# lcd-i2c.net
KiCad netlist of a schematic drawn in EAGLE
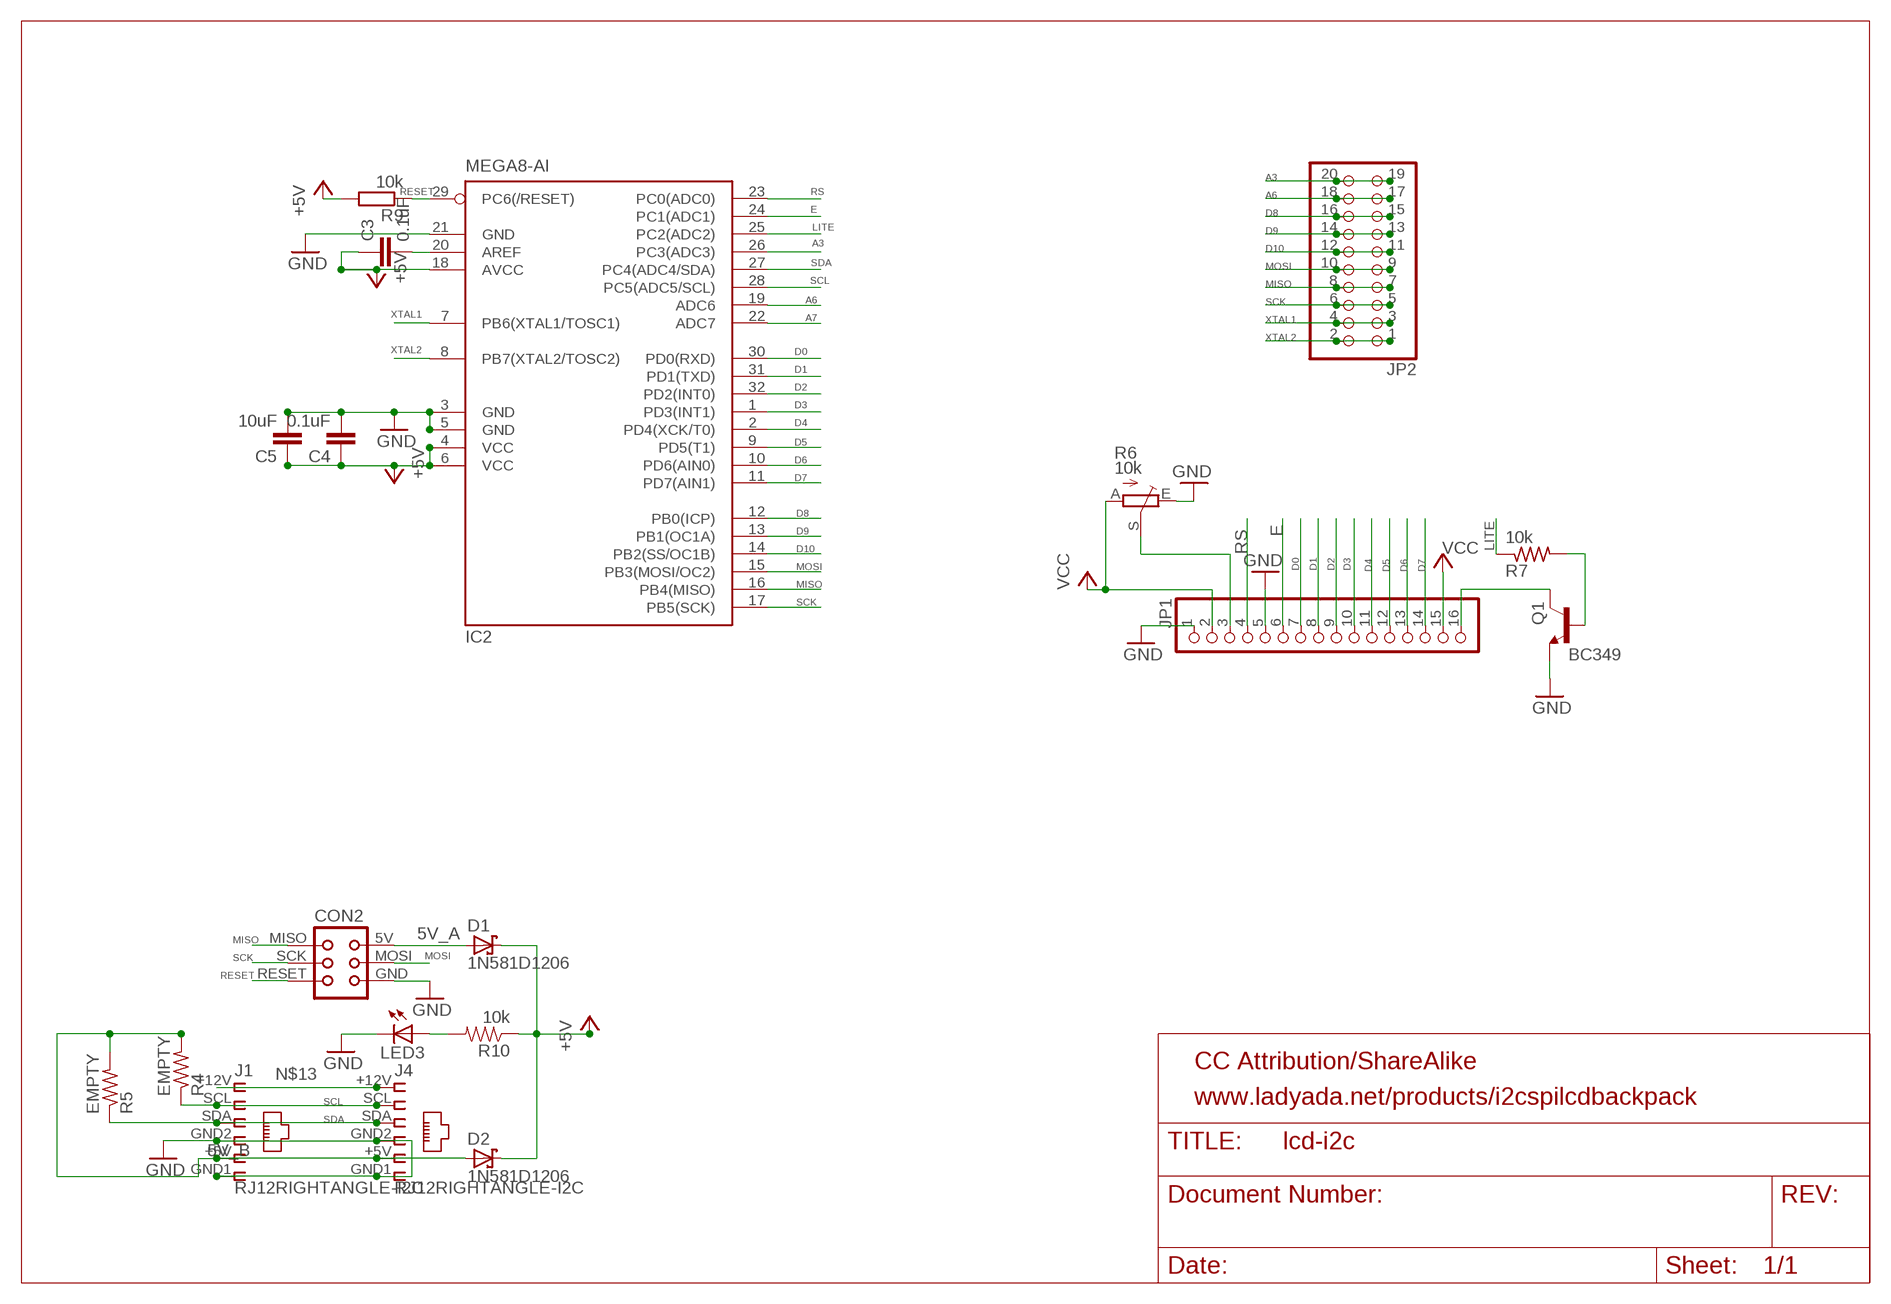
[diagram p0: schematic, sheet 1]

(export (version "E")
  (design (tool "Eeschema 10.0.6"))
  (components
    (comp (ref "C3")
      (value "0.1uF")
      (footprint "eagle-import:C1206")
      (libsource (lib "eagle-import") (part "C-EUC1206"))
    )
    (comp (ref "C4")
      (value "0.1uF")
      (footprint "eagle-import:C1206")
      (libsource (lib "eagle-import") (part "C-EUC1206"))
    )
    (comp (ref "C5")
      (value "10uF")
      (footprint "eagle-import:C1206")
      (libsource (lib "eagle-import") (part "C-EUC1206"))
    )
    (comp (ref "CON2")
      (value "TINYISPTAG")
      (footprint "eagle-import:TC2030-MCP")
      (libsource (lib "eagle-import") (part "TINYISPTAG"))
    )
    (comp (ref "D1")
      (value "1N581D1206")
      (footprint "eagle-import:LED-1206")
      (libsource (lib "eagle-import") (part "1N581D1206"))
    )
    (comp (ref "D2")
      (value "1N581D1206")
      (footprint "eagle-import:LED-1206")
      (libsource (lib "eagle-import") (part "1N581D1206"))
    )
    (comp (ref "IC2")
      (value "MEGA8-AI")
      (footprint "eagle-import:TQFP32-08")
      (fields (field (name "MPN") "ATMEGA8-16AU"))
      (libsource (lib "eagle-import") (part "MEGA8-AI"))
    )
    (comp (ref "J1")
      (value "RJ12RIGHTANGLE-I2C")
      (footprint "eagle-import:RJ12-RIGHTANGLE-I2C")
      (libsource (lib "eagle-import") (part "RJ12RIGHTANGLE-I2C"))
    )
    (comp (ref "J4")
      (value "RJ12RIGHTANGLE-I2C")
      (footprint "eagle-import:RJ12-RIGHTANGLE-I2C")
      (libsource (lib "eagle-import") (part "RJ12RIGHTANGLE-I2C"))
    )
    (comp (ref "JP1")
      (value "PINHD-1X16")
      (footprint "eagle-import:1X16")
      (libsource (lib "eagle-import") (part "PINHD-1X16"))
    )
    (comp (ref "JP2")
      (value "PINHD-2X10")
      (footprint "eagle-import:2X10")
      (libsource (lib "eagle-import") (part "PINHD-2X10"))
    )
    (comp (ref "LED3")
      (value "LEDCHIP-LED0603")
      (footprint "eagle-import:CHIP-LED0603")
      (libsource (lib "eagle-import") (part "LEDCHIP-LED0603"))
    )
    (comp (ref "Q1")
      (value "BC349")
      (footprint "eagle-import:TO92-EBC")
      (libsource (lib "eagle-import") (part "-NPN-TO92-EBCBC317"))
    )
    (comp (ref "R4")
      (value "EMPTY")
      (footprint "eagle-import:M1206")
      (libsource (lib "eagle-import") (part "R-US_M1206"))
    )
    (comp (ref "R5")
      (value "EMPTY")
      (footprint "eagle-import:M1206")
      (libsource (lib "eagle-import") (part "R-US_M1206"))
    )
    (comp (ref "R6")
      (value "10k")
      (footprint "eagle-import:CA6V")
      (libsource (lib "eagle-import") (part "TRIM_EU-CA6V"))
    )
    (comp (ref "R7")
      (value "10k")
      (footprint "eagle-import:M1206")
      (libsource (lib "eagle-import") (part "R-US_M1206"))
    )
    (comp (ref "R9")
      (value "10k")
      (footprint "eagle-import:M1206")
      (libsource (lib "eagle-import") (part "R-EU_M1206"))
    )
    (comp (ref "R10")
      (value "10k")
      (footprint "eagle-import:0603-RES")
      (libsource (lib "eagle-import") (part "RESISTOR0603-RES"))
    )
  )
  (nets
    (net (code "1") (name "+5V") (class "Default")
      (node (ref "C3") (pin "1") (pinfunction "1_1") (pintype "passive"))
      (node (ref "C4") (pin "1") (pinfunction "1_1") (pintype "passive"))
      (node (ref "C5") (pin "1") (pinfunction "1_1") (pintype "passive"))
      (node (ref "D1") (pin "C") (pinfunction "C_C") (pintype "passive"))
      (node (ref "D2") (pin "C") (pinfunction "C_C") (pintype "passive"))
      (node (ref "IC2") (pin "18") (pinfunction "AVCC_18") (pintype "power_in"))
      (node (ref "IC2") (pin "4") (pinfunction "VCC_4") (pintype "power_in"))
      (node (ref "IC2") (pin "6") (pinfunction "VCC_6") (pintype "power_in"))
      (node (ref "R10") (pin "1") (pinfunction "1_1") (pintype "passive"))
      (node (ref "R9") (pin "2") (pinfunction "2_2") (pintype "passive"))
    )
    (net (code "2") (name "/5V_A") (class "Default")
      (node (ref "CON2") (pin "5V") (pinfunction "VCC_5V") (pintype "passive"))
      (node (ref "D1") (pin "A") (pinfunction "A_A") (pintype "passive"))
    )
    (net (code "3") (name "/5V_B") (class "Default")
      (node (ref "D2") (pin "A") (pinfunction "A_A") (pintype "passive"))
      (node (ref "J1") (pin "+5V") (pinfunction "5_+5V") (pintype "bidirectional"))
      (node (ref "J4") (pin "+5V") (pinfunction "5_+5V") (pintype "bidirectional"))
      (node (ref "R4") (pin "2") (pinfunction "2_2") (pintype "passive"))
      (node (ref "R5") (pin "2") (pinfunction "2_2") (pintype "passive"))
    )
    (net (code "4") (name "/A3") (class "Default")
      (node (ref "IC2") (pin "26") (pinfunction "PC3(ADC3)_26") (pintype "bidirectional"))
      (node (ref "JP2") (pin "19") (pinfunction "19_19") (pintype "passive"))
      (node (ref "JP2") (pin "20") (pinfunction "20_20") (pintype "passive"))
    )
    (net (code "5") (name "/A6") (class "Default")
      (node (ref "IC2") (pin "19") (pinfunction "ADC6_19") (pintype "bidirectional"))
      (node (ref "JP2") (pin "17") (pinfunction "17_17") (pintype "passive"))
      (node (ref "JP2") (pin "18") (pinfunction "18_18") (pintype "passive"))
    )
    (net (code "6") (name "/A7") (class "Default")
      (node (ref "IC2") (pin "22") (pinfunction "ADC7_22") (pintype "bidirectional"))
    )
    (net (code "7") (name "/D0") (class "Default")
      (node (ref "IC2") (pin "30") (pinfunction "PD0(RXD)_30") (pintype "bidirectional"))
      (node (ref "JP1") (pin "7") (pinfunction "7_7") (pintype "passive"))
    )
    (net (code "8") (name "/D1") (class "Default")
      (node (ref "IC2") (pin "31") (pinfunction "PD1(TXD)_31") (pintype "bidirectional"))
      (node (ref "JP1") (pin "8") (pinfunction "8_8") (pintype "passive"))
    )
    (net (code "9") (name "/D2") (class "Default")
      (node (ref "IC2") (pin "32") (pinfunction "PD2(INT0)_32") (pintype "bidirectional"))
      (node (ref "JP1") (pin "9") (pinfunction "9_9") (pintype "passive"))
    )
    (net (code "10") (name "/D3") (class "Default")
      (node (ref "IC2") (pin "1") (pinfunction "PD3(INT1)_1") (pintype "bidirectional"))
      (node (ref "JP1") (pin "10") (pinfunction "10_10") (pintype "passive"))
    )
    (net (code "11") (name "/D4") (class "Default")
      (node (ref "IC2") (pin "2") (pinfunction "PD4(XCK/T0)_2") (pintype "bidirectional"))
      (node (ref "JP1") (pin "11") (pinfunction "11_11") (pintype "passive"))
    )
    (net (code "12") (name "/D5") (class "Default")
      (node (ref "IC2") (pin "9") (pinfunction "PD5(T1)_9") (pintype "bidirectional"))
      (node (ref "JP1") (pin "12") (pinfunction "12_12") (pintype "passive"))
    )
    (net (code "13") (name "/D6") (class "Default")
      (node (ref "IC2") (pin "10") (pinfunction "PD6(AIN0)_10") (pintype "bidirectional"))
      (node (ref "JP1") (pin "13") (pinfunction "13_13") (pintype "passive"))
    )
    (net (code "14") (name "/D7") (class "Default")
      (node (ref "IC2") (pin "11") (pinfunction "PD7(AIN1)_11") (pintype "bidirectional"))
      (node (ref "JP1") (pin "14") (pinfunction "14_14") (pintype "passive"))
    )
    (net (code "15") (name "/D8") (class "Default")
      (node (ref "IC2") (pin "12") (pinfunction "PB0(ICP)_12") (pintype "bidirectional"))
      (node (ref "JP2") (pin "15") (pinfunction "15_15") (pintype "passive"))
      (node (ref "JP2") (pin "16") (pinfunction "16_16") (pintype "passive"))
    )
    (net (code "16") (name "/D9") (class "Default")
      (node (ref "IC2") (pin "13") (pinfunction "PB1(OC1A)_13") (pintype "bidirectional"))
      (node (ref "JP2") (pin "13") (pinfunction "13_13") (pintype "passive"))
      (node (ref "JP2") (pin "14") (pinfunction "14_14") (pintype "passive"))
    )
    (net (code "17") (name "/D10") (class "Default")
      (node (ref "IC2") (pin "14") (pinfunction "PB2(SS/OC1B)_14") (pintype "bidirectional"))
      (node (ref "JP2") (pin "11") (pinfunction "11_11") (pintype "passive"))
      (node (ref "JP2") (pin "12") (pinfunction "12_12") (pintype "passive"))
    )
    (net (code "18") (name "/E") (class "Default")
      (node (ref "IC2") (pin "24") (pinfunction "PC1(ADC1)_24") (pintype "bidirectional"))
      (node (ref "JP1") (pin "6") (pinfunction "6_6") (pintype "passive"))
    )
    (net (code "19") (name "/LITE") (class "Default")
      (node (ref "IC2") (pin "25") (pinfunction "PC2(ADC2)_25") (pintype "bidirectional"))
      (node (ref "R7") (pin "1") (pinfunction "1_1") (pintype "passive"))
    )
    (net (code "20") (name "/MISO") (class "Default")
      (node (ref "CON2") (pin "MISO") (pinfunction "MISO_MISO") (pintype "passive"))
      (node (ref "IC2") (pin "16") (pinfunction "PB4(MISO)_16") (pintype "bidirectional"))
      (node (ref "JP2") (pin "7") (pinfunction "7_7") (pintype "passive"))
      (node (ref "JP2") (pin "8") (pinfunction "8_8") (pintype "passive"))
    )
    (net (code "21") (name "/MOSI") (class "Default")
      (node (ref "CON2") (pin "MOSI") (pinfunction "MOSI_MOSI") (pintype "passive"))
      (node (ref "IC2") (pin "15") (pinfunction "PB3(MOSI/OC2)_15") (pintype "bidirectional"))
      (node (ref "JP2") (pin "10") (pinfunction "10_10") (pintype "passive"))
      (node (ref "JP2") (pin "9") (pinfunction "9_9") (pintype "passive"))
    )
    (net (code "22") (name "/N$13") (class "Default")
      (node (ref "J1") (pin "+12V") (pinfunction "1_+12V") (pintype "bidirectional"))
      (node (ref "J4") (pin "+12V") (pinfunction "1_+12V") (pintype "bidirectional"))
    )
    (net (code "23") (name "/RESET") (class "Default")
      (node (ref "CON2") (pin "RESET") (pinfunction "RESET_RESET") (pintype "passive"))
      (node (ref "IC2") (pin "29") (pinfunction "PC6(/RESET)_29") (pintype "bidirectional"))
      (node (ref "R9") (pin "1") (pinfunction "1_1") (pintype "passive"))
    )
    (net (code "24") (name "/RS") (class "Default")
      (node (ref "IC2") (pin "23") (pinfunction "PC0(ADC0)_23") (pintype "bidirectional"))
      (node (ref "JP1") (pin "4") (pinfunction "4_4") (pintype "passive"))
    )
    (net (code "25") (name "/SCK") (class "Default")
      (node (ref "CON2") (pin "SCK") (pinfunction "SCK_SCK") (pintype "passive"))
      (node (ref "IC2") (pin "17") (pinfunction "PB5(SCK)_17") (pintype "bidirectional"))
      (node (ref "JP2") (pin "5") (pinfunction "5_5") (pintype "passive"))
      (node (ref "JP2") (pin "6") (pinfunction "6_6") (pintype "passive"))
    )
    (net (code "26") (name "/SCL") (class "Default")
      (node (ref "IC2") (pin "28") (pinfunction "PC5(ADC5/SCL)_28") (pintype "bidirectional"))
      (node (ref "J1") (pin "SCL") (pinfunction "2_SCL") (pintype "bidirectional"))
      (node (ref "J4") (pin "SCL") (pinfunction "2_SCL") (pintype "bidirectional"))
      (node (ref "R4") (pin "1") (pinfunction "1_1") (pintype "passive"))
    )
    (net (code "27") (name "/SDA") (class "Default")
      (node (ref "IC2") (pin "27") (pinfunction "PC4(ADC4/SDA)_27") (pintype "bidirectional"))
      (node (ref "J1") (pin "SDA") (pinfunction "3_SDA") (pintype "bidirectional"))
      (node (ref "J4") (pin "SDA") (pinfunction "3_SDA") (pintype "bidirectional"))
      (node (ref "R5") (pin "1") (pinfunction "1_1") (pintype "passive"))
    )
    (net (code "28") (name "/XTAL1") (class "Default")
      (node (ref "IC2") (pin "7") (pinfunction "PB6(XTAL1/TOSC1)_7") (pintype "bidirectional"))
      (node (ref "JP2") (pin "3") (pinfunction "3_3") (pintype "passive"))
      (node (ref "JP2") (pin "4") (pinfunction "4_4") (pintype "passive"))
    )
    (net (code "29") (name "/XTAL2") (class "Default")
      (node (ref "IC2") (pin "8") (pinfunction "PB7(XTAL2/TOSC2)_8") (pintype "bidirectional"))
      (node (ref "JP2") (pin "1") (pinfunction "1_1") (pintype "passive"))
      (node (ref "JP2") (pin "2") (pinfunction "2_2") (pintype "passive"))
    )
    (net (code "30") (name "GND") (class "Default")
      (node (ref "C4") (pin "2") (pinfunction "2_2") (pintype "passive"))
      (node (ref "C5") (pin "2") (pinfunction "2_2") (pintype "passive"))
      (node (ref "CON2") (pin "GND") (pinfunction "GND_GND") (pintype "passive"))
      (node (ref "IC2") (pin "21") (pinfunction "GND_21") (pintype "power_in"))
      (node (ref "IC2") (pin "3") (pinfunction "GND_3") (pintype "power_in"))
      (node (ref "IC2") (pin "5") (pinfunction "GND_5") (pintype "power_in"))
      (node (ref "J1") (pin "GND1") (pinfunction "6_GND1") (pintype "bidirectional"))
      (node (ref "J1") (pin "GND2") (pinfunction "4_GND2") (pintype "bidirectional"))
      (node (ref "J4") (pin "GND1") (pinfunction "6_GND1") (pintype "bidirectional"))
      (node (ref "J4") (pin "GND2") (pinfunction "4_GND2") (pintype "bidirectional"))
      (node (ref "JP1") (pin "1") (pinfunction "1_1") (pintype "passive"))
      (node (ref "JP1") (pin "5") (pinfunction "5_5") (pintype "passive"))
      (node (ref "LED3") (pin "C") (pinfunction "C_C") (pintype "passive"))
      (node (ref "Q1") (pin "E") (pinfunction "E_E") (pintype "passive"))
      (node (ref "R6") (pin "E") (pinfunction "E_E") (pintype "passive"))
    )
    (net (code "31") (name "Net-(IC2-AREF)") (class "Default")
      (node (ref "C3") (pin "2") (pinfunction "2_2") (pintype "passive"))
      (node (ref "IC2") (pin "20") (pinfunction "AREF_20") (pintype "passive"))
    )
    (net (code "32") (name "Net-(JP1-Pad3)") (class "Default")
      (node (ref "JP1") (pin "3") (pinfunction "3_3") (pintype "passive"))
      (node (ref "R6") (pin "S") (pinfunction "S_S") (pintype "passive"))
    )
    (net (code "33") (name "Net-(JP1-Pad16)") (class "Default")
      (node (ref "JP1") (pin "16") (pinfunction "16_16") (pintype "passive"))
      (node (ref "Q1") (pin "C") (pinfunction "C_C") (pintype "passive"))
    )
    (net (code "34") (name "Net-(LED3-PadA)") (class "Default")
      (node (ref "LED3") (pin "A") (pinfunction "A_A") (pintype "passive"))
      (node (ref "R10") (pin "2") (pinfunction "2_2") (pintype "passive"))
    )
    (net (code "35") (name "Net-(Q1-PadB)") (class "Default")
      (node (ref "Q1") (pin "B") (pinfunction "B_B") (pintype "passive"))
      (node (ref "R7") (pin "2") (pinfunction "2_2") (pintype "passive"))
    )
    (net (code "36") (name "VCC") (class "Default")
      (node (ref "JP1") (pin "15") (pinfunction "15_15") (pintype "passive"))
      (node (ref "JP1") (pin "2") (pinfunction "2_2") (pintype "passive"))
      (node (ref "R6") (pin "A") (pinfunction "A_A") (pintype "passive"))
    )
  )
)
